# C64_ProtoBreakOut_Stabilized.net
KiCad netlist of a schematic drawn in EAGLE
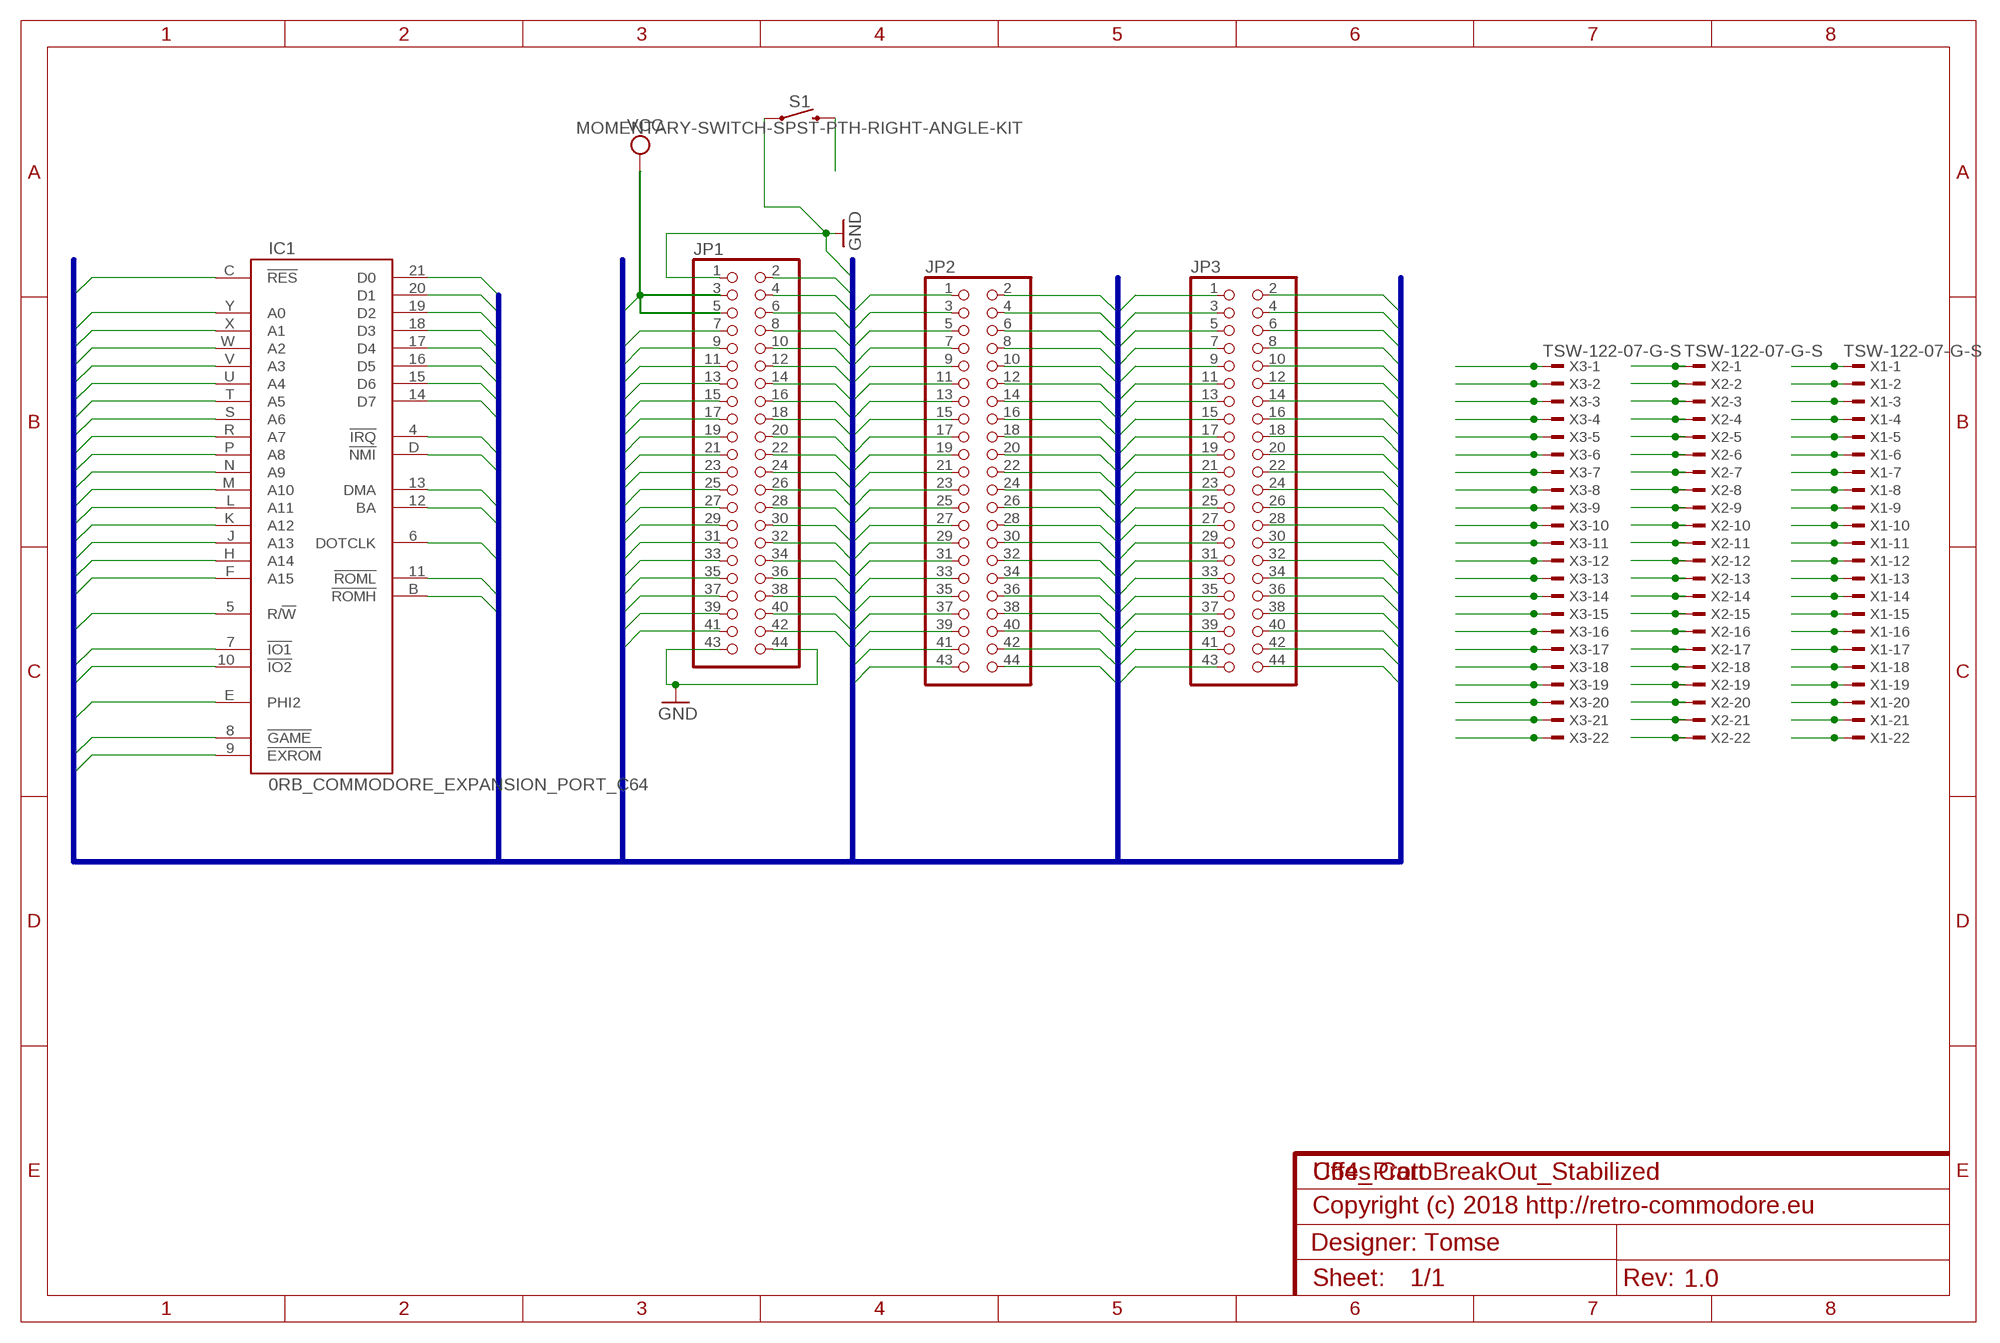
[diagram p0: schematic, sheet 1]

(export (version "E")
  (design (tool "Eeschema 10.0.6"))
  (components
    (comp (ref "IC1")
      (value "0RB_COMMODORE_EXPANSION_PORT_C64")
      (footprint "eagle-import:0RB_COMMODORE_MA100-22-2")
      (libsource (lib "eagle-import") (part "0RB_COMMODORE_EXPANSION_PORT_C64"))
    )
    (comp (ref "JP1")
      (value "PINHD-2X22")
      (footprint "eagle-import:2X22")
      (libsource (lib "eagle-import") (part "PINHD-2X22"))
    )
    (comp (ref "JP2")
      (value "PINHD-2X22")
      (footprint "eagle-import:2X22")
      (libsource (lib "eagle-import") (part "PINHD-2X22"))
    )
    (comp (ref "JP3")
      (value "PINHD-2X22")
      (footprint "eagle-import:2X22")
      (libsource (lib "eagle-import") (part "PINHD-2X22"))
    )
    (comp (ref "S1")
      (value "MOMENTARY-SWITCH-SPST-PTH-RIGHT-ANGLE-KIT")
      (footprint "eagle-import:TACTILE_SWITCH_PTH_RIGHT_ANGLE_KIT")
      (libsource (lib "eagle-import") (part "MOMENTARY-SWITCH-SPST-PTH-RIGHT-ANGLE-KIT"))
    )
    (comp (ref "X1")
      (value "TSW-122-07-G-S")
      (footprint "eagle-import:TSW-122-XX-G-S")
      (fields (field (name "MF") "Samtec Inc."))
      (libsource (lib "eagle-import") (part "TSW-122--G-S07"))
    )
    (comp (ref "X2")
      (value "TSW-122-07-G-S")
      (footprint "eagle-import:TSW-122-XX-G-S")
      (fields (field (name "MF") "Samtec Inc."))
      (libsource (lib "eagle-import") (part "TSW-122--G-S07"))
    )
    (comp (ref "X3")
      (value "TSW-122-07-G-S")
      (footprint "eagle-import:TSW-122-XX-G-S")
      (fields (field (name "MF") "Samtec Inc."))
      (libsource (lib "eagle-import") (part "TSW-122--G-S07"))
    )
  )
  (nets
    (net (code "1") (name "/A0") (class "Default")
      (node (ref "IC1") (pin "Y") (pinfunction "A0_Y") (pintype "bidirectional"))
      (node (ref "JP1") (pin "42") (pinfunction "42_42") (pintype "passive"))
      (node (ref "JP2") (pin "42") (pinfunction "42_42") (pintype "passive"))
      (node (ref "JP3") (pin "42") (pinfunction "42_42") (pintype "passive"))
    )
    (net (code "2") (name "/A1") (class "Default")
      (node (ref "IC1") (pin "X") (pinfunction "A1_X") (pintype "bidirectional"))
      (node (ref "JP1") (pin "40") (pinfunction "40_40") (pintype "passive"))
      (node (ref "JP2") (pin "40") (pinfunction "40_40") (pintype "passive"))
      (node (ref "JP3") (pin "40") (pinfunction "40_40") (pintype "passive"))
    )
    (net (code "3") (name "/A2") (class "Default")
      (node (ref "IC1") (pin "W") (pinfunction "A2_W") (pintype "bidirectional"))
      (node (ref "JP1") (pin "38") (pinfunction "38_38") (pintype "passive"))
      (node (ref "JP2") (pin "38") (pinfunction "38_38") (pintype "passive"))
      (node (ref "JP3") (pin "38") (pinfunction "38_38") (pintype "passive"))
    )
    (net (code "4") (name "/A3") (class "Default")
      (node (ref "IC1") (pin "V") (pinfunction "A3_V") (pintype "bidirectional"))
      (node (ref "JP1") (pin "36") (pinfunction "36_36") (pintype "passive"))
      (node (ref "JP2") (pin "36") (pinfunction "36_36") (pintype "passive"))
      (node (ref "JP3") (pin "36") (pinfunction "36_36") (pintype "passive"))
    )
    (net (code "5") (name "/A4") (class "Default")
      (node (ref "IC1") (pin "U") (pinfunction "A4_U") (pintype "bidirectional"))
      (node (ref "JP1") (pin "34") (pinfunction "34_34") (pintype "passive"))
      (node (ref "JP2") (pin "34") (pinfunction "34_34") (pintype "passive"))
      (node (ref "JP3") (pin "34") (pinfunction "34_34") (pintype "passive"))
    )
    (net (code "6") (name "/A5") (class "Default")
      (node (ref "IC1") (pin "T") (pinfunction "A5_T") (pintype "bidirectional"))
      (node (ref "JP1") (pin "32") (pinfunction "32_32") (pintype "passive"))
      (node (ref "JP2") (pin "32") (pinfunction "32_32") (pintype "passive"))
      (node (ref "JP3") (pin "32") (pinfunction "32_32") (pintype "passive"))
    )
    (net (code "7") (name "/A6") (class "Default")
      (node (ref "IC1") (pin "S") (pinfunction "A6_S") (pintype "bidirectional"))
      (node (ref "JP1") (pin "30") (pinfunction "30_30") (pintype "passive"))
      (node (ref "JP2") (pin "30") (pinfunction "30_30") (pintype "passive"))
      (node (ref "JP3") (pin "30") (pinfunction "30_30") (pintype "passive"))
    )
    (net (code "8") (name "/A7") (class "Default")
      (node (ref "IC1") (pin "R") (pinfunction "A7_R") (pintype "bidirectional"))
      (node (ref "JP1") (pin "28") (pinfunction "28_28") (pintype "passive"))
      (node (ref "JP2") (pin "28") (pinfunction "28_28") (pintype "passive"))
      (node (ref "JP3") (pin "28") (pinfunction "28_28") (pintype "passive"))
    )
    (net (code "9") (name "/A8") (class "Default")
      (node (ref "IC1") (pin "P") (pinfunction "A8_P") (pintype "bidirectional"))
      (node (ref "JP1") (pin "26") (pinfunction "26_26") (pintype "passive"))
      (node (ref "JP2") (pin "26") (pinfunction "26_26") (pintype "passive"))
      (node (ref "JP3") (pin "26") (pinfunction "26_26") (pintype "passive"))
    )
    (net (code "10") (name "/A9") (class "Default")
      (node (ref "IC1") (pin "N") (pinfunction "A9_N") (pintype "bidirectional"))
      (node (ref "JP1") (pin "24") (pinfunction "24_24") (pintype "passive"))
      (node (ref "JP2") (pin "24") (pinfunction "24_24") (pintype "passive"))
      (node (ref "JP3") (pin "24") (pinfunction "24_24") (pintype "passive"))
    )
    (net (code "11") (name "/A10") (class "Default")
      (node (ref "IC1") (pin "M") (pinfunction "A10_M") (pintype "bidirectional"))
      (node (ref "JP1") (pin "22") (pinfunction "22_22") (pintype "passive"))
      (node (ref "JP2") (pin "22") (pinfunction "22_22") (pintype "passive"))
      (node (ref "JP3") (pin "22") (pinfunction "22_22") (pintype "passive"))
    )
    (net (code "12") (name "/A11") (class "Default")
      (node (ref "IC1") (pin "L") (pinfunction "A11_L") (pintype "bidirectional"))
      (node (ref "JP1") (pin "20") (pinfunction "20_20") (pintype "passive"))
      (node (ref "JP2") (pin "20") (pinfunction "20_20") (pintype "passive"))
      (node (ref "JP3") (pin "20") (pinfunction "20_20") (pintype "passive"))
    )
    (net (code "13") (name "/A12") (class "Default")
      (node (ref "IC1") (pin "K") (pinfunction "A12_K") (pintype "bidirectional"))
      (node (ref "JP1") (pin "18") (pinfunction "18_18") (pintype "passive"))
      (node (ref "JP2") (pin "18") (pinfunction "18_18") (pintype "passive"))
      (node (ref "JP3") (pin "18") (pinfunction "18_18") (pintype "passive"))
    )
    (net (code "14") (name "/A13") (class "Default")
      (node (ref "IC1") (pin "J") (pinfunction "A13_J") (pintype "bidirectional"))
      (node (ref "JP1") (pin "16") (pinfunction "16_16") (pintype "passive"))
      (node (ref "JP2") (pin "16") (pinfunction "16_16") (pintype "passive"))
      (node (ref "JP3") (pin "16") (pinfunction "16_16") (pintype "passive"))
    )
    (net (code "15") (name "/A14") (class "Default")
      (node (ref "IC1") (pin "H") (pinfunction "A14_H") (pintype "bidirectional"))
      (node (ref "JP1") (pin "14") (pinfunction "14_14") (pintype "passive"))
      (node (ref "JP2") (pin "14") (pinfunction "14_14") (pintype "passive"))
      (node (ref "JP3") (pin "14") (pinfunction "14_14") (pintype "passive"))
    )
    (net (code "16") (name "/A15") (class "Default")
      (node (ref "IC1") (pin "F") (pinfunction "A15_F") (pintype "bidirectional"))
      (node (ref "JP1") (pin "12") (pinfunction "12_12") (pintype "passive"))
      (node (ref "JP2") (pin "12") (pinfunction "12_12") (pintype "passive"))
      (node (ref "JP3") (pin "12") (pinfunction "12_12") (pintype "passive"))
    )
    (net (code "17") (name "/BA") (class "Default")
      (node (ref "IC1") (pin "12") (pinfunction "BA_12") (pintype "output"))
      (node (ref "JP1") (pin "23") (pinfunction "23_23") (pintype "passive"))
      (node (ref "JP2") (pin "23") (pinfunction "23_23") (pintype "passive"))
      (node (ref "JP3") (pin "23") (pinfunction "23_23") (pintype "passive"))
      (node (ref "X1") (pin "12") (pinfunction "1_12") (pintype "passive"))
      (node (ref "X2") (pin "12") (pinfunction "1_12") (pintype "passive"))
      (node (ref "X3") (pin "12") (pinfunction "1_12") (pintype "passive"))
    )
    (net (code "18") (name "/D0") (class "Default")
      (node (ref "IC1") (pin "21") (pinfunction "D0_21") (pintype "bidirectional"))
      (node (ref "JP1") (pin "41") (pinfunction "41_41") (pintype "passive"))
      (node (ref "JP2") (pin "41") (pinfunction "41_41") (pintype "passive"))
      (node (ref "JP3") (pin "41") (pinfunction "41_41") (pintype "passive"))
      (node (ref "X1") (pin "21") (pinfunction "1_21") (pintype "passive"))
      (node (ref "X2") (pin "21") (pinfunction "1_21") (pintype "passive"))
      (node (ref "X3") (pin "21") (pinfunction "1_21") (pintype "passive"))
    )
    (net (code "19") (name "/D1") (class "Default")
      (node (ref "IC1") (pin "20") (pinfunction "D1_20") (pintype "bidirectional"))
      (node (ref "JP1") (pin "39") (pinfunction "39_39") (pintype "passive"))
      (node (ref "JP2") (pin "39") (pinfunction "39_39") (pintype "passive"))
      (node (ref "JP3") (pin "39") (pinfunction "39_39") (pintype "passive"))
      (node (ref "X1") (pin "20") (pinfunction "1_20") (pintype "passive"))
      (node (ref "X2") (pin "20") (pinfunction "1_20") (pintype "passive"))
      (node (ref "X3") (pin "20") (pinfunction "1_20") (pintype "passive"))
    )
    (net (code "20") (name "/D2") (class "Default")
      (node (ref "IC1") (pin "19") (pinfunction "D2_19") (pintype "bidirectional"))
      (node (ref "JP1") (pin "37") (pinfunction "37_37") (pintype "passive"))
      (node (ref "JP2") (pin "37") (pinfunction "37_37") (pintype "passive"))
      (node (ref "JP3") (pin "37") (pinfunction "37_37") (pintype "passive"))
      (node (ref "X1") (pin "19") (pinfunction "1_19") (pintype "passive"))
      (node (ref "X2") (pin "19") (pinfunction "1_19") (pintype "passive"))
      (node (ref "X3") (pin "19") (pinfunction "1_19") (pintype "passive"))
    )
    (net (code "21") (name "/D3") (class "Default")
      (node (ref "IC1") (pin "18") (pinfunction "D3_18") (pintype "bidirectional"))
      (node (ref "JP1") (pin "35") (pinfunction "35_35") (pintype "passive"))
      (node (ref "JP2") (pin "35") (pinfunction "35_35") (pintype "passive"))
      (node (ref "JP3") (pin "35") (pinfunction "35_35") (pintype "passive"))
      (node (ref "X1") (pin "18") (pinfunction "1_18") (pintype "passive"))
      (node (ref "X2") (pin "18") (pinfunction "1_18") (pintype "passive"))
      (node (ref "X3") (pin "18") (pinfunction "1_18") (pintype "passive"))
    )
    (net (code "22") (name "/D4") (class "Default")
      (node (ref "IC1") (pin "17") (pinfunction "D4_17") (pintype "bidirectional"))
      (node (ref "JP1") (pin "33") (pinfunction "33_33") (pintype "passive"))
      (node (ref "JP2") (pin "33") (pinfunction "33_33") (pintype "passive"))
      (node (ref "JP3") (pin "33") (pinfunction "33_33") (pintype "passive"))
      (node (ref "X1") (pin "17") (pinfunction "1_17") (pintype "passive"))
      (node (ref "X2") (pin "17") (pinfunction "1_17") (pintype "passive"))
      (node (ref "X3") (pin "17") (pinfunction "1_17") (pintype "passive"))
    )
    (net (code "23") (name "/D5") (class "Default")
      (node (ref "IC1") (pin "16") (pinfunction "D5_16") (pintype "bidirectional"))
      (node (ref "JP1") (pin "31") (pinfunction "31_31") (pintype "passive"))
      (node (ref "JP2") (pin "31") (pinfunction "31_31") (pintype "passive"))
      (node (ref "JP3") (pin "31") (pinfunction "31_31") (pintype "passive"))
      (node (ref "X1") (pin "16") (pinfunction "1_16") (pintype "passive"))
      (node (ref "X2") (pin "16") (pinfunction "1_16") (pintype "passive"))
      (node (ref "X3") (pin "16") (pinfunction "1_16") (pintype "passive"))
    )
    (net (code "24") (name "/D6") (class "Default")
      (node (ref "IC1") (pin "15") (pinfunction "D6_15") (pintype "bidirectional"))
      (node (ref "JP1") (pin "29") (pinfunction "29_29") (pintype "passive"))
      (node (ref "JP2") (pin "29") (pinfunction "29_29") (pintype "passive"))
      (node (ref "JP3") (pin "29") (pinfunction "29_29") (pintype "passive"))
      (node (ref "X1") (pin "15") (pinfunction "1_15") (pintype "passive"))
      (node (ref "X2") (pin "15") (pinfunction "1_15") (pintype "passive"))
      (node (ref "X3") (pin "15") (pinfunction "1_15") (pintype "passive"))
    )
    (net (code "25") (name "/D7") (class "Default")
      (node (ref "IC1") (pin "14") (pinfunction "D7_14") (pintype "bidirectional"))
      (node (ref "JP1") (pin "27") (pinfunction "27_27") (pintype "passive"))
      (node (ref "JP2") (pin "27") (pinfunction "27_27") (pintype "passive"))
      (node (ref "JP3") (pin "27") (pinfunction "27_27") (pintype "passive"))
      (node (ref "X1") (pin "14") (pinfunction "1_14") (pintype "passive"))
      (node (ref "X2") (pin "14") (pinfunction "1_14") (pintype "passive"))
      (node (ref "X3") (pin "14") (pinfunction "1_14") (pintype "passive"))
    )
    (net (code "26") (name "/DOTCLK") (class "Default")
      (node (ref "IC1") (pin "6") (pinfunction "DOTCLK_6") (pintype "output"))
      (node (ref "JP1") (pin "11") (pinfunction "11_11") (pintype "passive"))
      (node (ref "JP2") (pin "11") (pinfunction "11_11") (pintype "passive"))
      (node (ref "JP3") (pin "11") (pinfunction "11_11") (pintype "passive"))
      (node (ref "X1") (pin "6") (pinfunction "1_6") (pintype "passive"))
      (node (ref "X2") (pin "6") (pinfunction "1_6") (pintype "passive"))
      (node (ref "X3") (pin "6") (pinfunction "1_6") (pintype "passive"))
    )
    (net (code "27") (name "/PHI2") (class "Default")
      (node (ref "IC1") (pin "E") (pinfunction "PHI2_E") (pintype "output"))
      (node (ref "JP1") (pin "10") (pinfunction "10_10") (pintype "passive"))
      (node (ref "JP2") (pin "10") (pinfunction "10_10") (pintype "passive"))
      (node (ref "JP3") (pin "10") (pinfunction "10_10") (pintype "passive"))
    )
    (net (code "28") (name "/R~{W}") (class "Default")
      (node (ref "IC1") (pin "5") (pinfunction "R/~{W}_5") (pintype "bidirectional"))
      (node (ref "JP1") (pin "9") (pinfunction "9_9") (pintype "passive"))
      (node (ref "JP2") (pin "9") (pinfunction "9_9") (pintype "passive"))
      (node (ref "JP3") (pin "9") (pinfunction "9_9") (pintype "passive"))
      (node (ref "X1") (pin "5") (pinfunction "1_5") (pintype "passive"))
      (node (ref "X2") (pin "5") (pinfunction "1_5") (pintype "passive"))
      (node (ref "X3") (pin "5") (pinfunction "1_5") (pintype "passive"))
    )
    (net (code "29") (name "/~{DMA}") (class "Default")
      (node (ref "IC1") (pin "13") (pinfunction "DMA_13") (pintype "passive"))
      (node (ref "JP1") (pin "25") (pinfunction "25_25") (pintype "passive"))
      (node (ref "JP2") (pin "25") (pinfunction "25_25") (pintype "passive"))
      (node (ref "JP3") (pin "25") (pinfunction "25_25") (pintype "passive"))
      (node (ref "X1") (pin "13") (pinfunction "1_13") (pintype "passive"))
      (node (ref "X2") (pin "13") (pinfunction "1_13") (pintype "passive"))
      (node (ref "X3") (pin "13") (pinfunction "1_13") (pintype "passive"))
    )
    (net (code "30") (name "/~{EXROM}") (class "Default")
      (node (ref "IC1") (pin "9") (pinfunction "~{EXROM}_9") (pintype "passive"))
      (node (ref "JP1") (pin "17") (pinfunction "17_17") (pintype "passive"))
      (node (ref "JP2") (pin "17") (pinfunction "17_17") (pintype "passive"))
      (node (ref "JP3") (pin "17") (pinfunction "17_17") (pintype "passive"))
      (node (ref "X1") (pin "9") (pinfunction "1_9") (pintype "passive"))
      (node (ref "X2") (pin "9") (pinfunction "1_9") (pintype "passive"))
      (node (ref "X3") (pin "9") (pinfunction "1_9") (pintype "passive"))
    )
    (net (code "31") (name "/~{GAME}") (class "Default")
      (node (ref "IC1") (pin "8") (pinfunction "~{GAME}_8") (pintype "passive"))
      (node (ref "JP1") (pin "15") (pinfunction "15_15") (pintype "passive"))
      (node (ref "JP2") (pin "15") (pinfunction "15_15") (pintype "passive"))
      (node (ref "JP3") (pin "15") (pinfunction "15_15") (pintype "passive"))
      (node (ref "X1") (pin "8") (pinfunction "1_8") (pintype "passive"))
      (node (ref "X2") (pin "8") (pinfunction "1_8") (pintype "passive"))
      (node (ref "X3") (pin "8") (pinfunction "1_8") (pintype "passive"))
    )
    (net (code "32") (name "/~{IO1}") (class "Default")
      (node (ref "IC1") (pin "7") (pinfunction "~{IO1}_7") (pintype "output"))
      (node (ref "JP1") (pin "13") (pinfunction "13_13") (pintype "passive"))
      (node (ref "JP2") (pin "13") (pinfunction "13_13") (pintype "passive"))
      (node (ref "JP3") (pin "13") (pinfunction "13_13") (pintype "passive"))
      (node (ref "X1") (pin "7") (pinfunction "1_7") (pintype "passive"))
      (node (ref "X2") (pin "7") (pinfunction "1_7") (pintype "passive"))
      (node (ref "X3") (pin "7") (pinfunction "1_7") (pintype "passive"))
    )
    (net (code "33") (name "/~{IO2}") (class "Default")
      (node (ref "IC1") (pin "10") (pinfunction "~{IO2}_10") (pintype "output"))
      (node (ref "JP1") (pin "19") (pinfunction "19_19") (pintype "passive"))
      (node (ref "JP2") (pin "19") (pinfunction "19_19") (pintype "passive"))
      (node (ref "JP3") (pin "19") (pinfunction "19_19") (pintype "passive"))
      (node (ref "X1") (pin "10") (pinfunction "1_10") (pintype "passive"))
      (node (ref "X2") (pin "10") (pinfunction "1_10") (pintype "passive"))
      (node (ref "X3") (pin "10") (pinfunction "1_10") (pintype "passive"))
    )
    (net (code "34") (name "/~{IRQ}") (class "Default")
      (node (ref "IC1") (pin "4") (pinfunction "~{IRQ}_4") (pintype "passive"))
      (node (ref "JP1") (pin "7") (pinfunction "7_7") (pintype "passive"))
      (node (ref "JP2") (pin "7") (pinfunction "7_7") (pintype "passive"))
      (node (ref "JP3") (pin "7") (pinfunction "7_7") (pintype "passive"))
      (node (ref "X1") (pin "4") (pinfunction "1_4") (pintype "passive"))
      (node (ref "X2") (pin "4") (pinfunction "1_4") (pintype "passive"))
      (node (ref "X3") (pin "4") (pinfunction "1_4") (pintype "passive"))
    )
    (net (code "35") (name "/~{NMI}") (class "Default")
      (node (ref "IC1") (pin "D") (pinfunction "~{NMI}_D") (pintype "passive"))
      (node (ref "JP1") (pin "8") (pinfunction "8_8") (pintype "passive"))
      (node (ref "JP2") (pin "8") (pinfunction "8_8") (pintype "passive"))
      (node (ref "JP3") (pin "8") (pinfunction "8_8") (pintype "passive"))
    )
    (net (code "36") (name "/~{RES}") (class "Default")
      (node (ref "IC1") (pin "C") (pinfunction "~{RES}_C") (pintype "passive"))
      (node (ref "JP1") (pin "6") (pinfunction "6_6") (pintype "passive"))
      (node (ref "JP2") (pin "6") (pinfunction "6_6") (pintype "passive"))
      (node (ref "JP3") (pin "6") (pinfunction "6_6") (pintype "passive"))
      (node (ref "S1") (pin "2") (pinfunction "2_2") (pintype "passive"))
    )
    (net (code "37") (name "/~{ROMH}") (class "Default")
      (node (ref "IC1") (pin "B") (pinfunction "~{ROMH}_B") (pintype "output"))
      (node (ref "JP1") (pin "4") (pinfunction "4_4") (pintype "passive"))
      (node (ref "JP2") (pin "4") (pinfunction "4_4") (pintype "passive"))
      (node (ref "JP3") (pin "4") (pinfunction "4_4") (pintype "passive"))
    )
    (net (code "38") (name "/~{ROML}") (class "Default")
      (node (ref "IC1") (pin "11") (pinfunction "~{ROML}_11") (pintype "output"))
      (node (ref "JP1") (pin "21") (pinfunction "21_21") (pintype "passive"))
      (node (ref "JP2") (pin "21") (pinfunction "21_21") (pintype "passive"))
      (node (ref "JP3") (pin "21") (pinfunction "21_21") (pintype "passive"))
      (node (ref "X1") (pin "11") (pinfunction "1_11") (pintype "passive"))
      (node (ref "X2") (pin "11") (pinfunction "1_11") (pintype "passive"))
      (node (ref "X3") (pin "11") (pinfunction "1_11") (pintype "passive"))
    )
    (net (code "39") (name "GND") (class "Default")
      (node (ref "JP1") (pin "1") (pinfunction "1_1") (pintype "passive"))
      (node (ref "JP1") (pin "2") (pinfunction "2_2") (pintype "passive"))
      (node (ref "JP1") (pin "43") (pinfunction "43_43") (pintype "passive"))
      (node (ref "JP1") (pin "44") (pinfunction "44_44") (pintype "passive"))
      (node (ref "JP2") (pin "1") (pinfunction "1_1") (pintype "passive"))
      (node (ref "JP2") (pin "2") (pinfunction "2_2") (pintype "passive"))
      (node (ref "JP2") (pin "43") (pinfunction "43_43") (pintype "passive"))
      (node (ref "JP2") (pin "44") (pinfunction "44_44") (pintype "passive"))
      (node (ref "JP3") (pin "1") (pinfunction "1_1") (pintype "passive"))
      (node (ref "JP3") (pin "2") (pinfunction "2_2") (pintype "passive"))
      (node (ref "JP3") (pin "43") (pinfunction "43_43") (pintype "passive"))
      (node (ref "JP3") (pin "44") (pinfunction "44_44") (pintype "passive"))
      (node (ref "S1") (pin "1") (pinfunction "1_1") (pintype "passive"))
      (node (ref "X1") (pin "1") (pinfunction "1_1") (pintype "passive"))
      (node (ref "X1") (pin "22") (pinfunction "1_22") (pintype "passive"))
      (node (ref "X2") (pin "1") (pinfunction "1_1") (pintype "passive"))
      (node (ref "X2") (pin "22") (pinfunction "1_22") (pintype "passive"))
      (node (ref "X3") (pin "1") (pinfunction "1_1") (pintype "passive"))
      (node (ref "X3") (pin "22") (pinfunction "1_22") (pintype "passive"))
    )
    (net (code "40") (name "VCC") (class "Default")
      (node (ref "JP1") (pin "3") (pinfunction "3_3") (pintype "passive"))
      (node (ref "JP1") (pin "5") (pinfunction "5_5") (pintype "passive"))
      (node (ref "JP2") (pin "3") (pinfunction "3_3") (pintype "passive"))
      (node (ref "JP2") (pin "5") (pinfunction "5_5") (pintype "passive"))
      (node (ref "JP3") (pin "3") (pinfunction "3_3") (pintype "passive"))
      (node (ref "JP3") (pin "5") (pinfunction "5_5") (pintype "passive"))
      (node (ref "X1") (pin "2") (pinfunction "1_2") (pintype "passive"))
      (node (ref "X1") (pin "3") (pinfunction "1_3") (pintype "passive"))
      (node (ref "X2") (pin "2") (pinfunction "1_2") (pintype "passive"))
      (node (ref "X2") (pin "3") (pinfunction "1_3") (pintype "passive"))
      (node (ref "X3") (pin "2") (pinfunction "1_2") (pintype "passive"))
      (node (ref "X3") (pin "3") (pinfunction "1_3") (pintype "passive"))
    )
  )
)
